# untitled.net
KiCad netlist of a schematic drawn in EAGLE
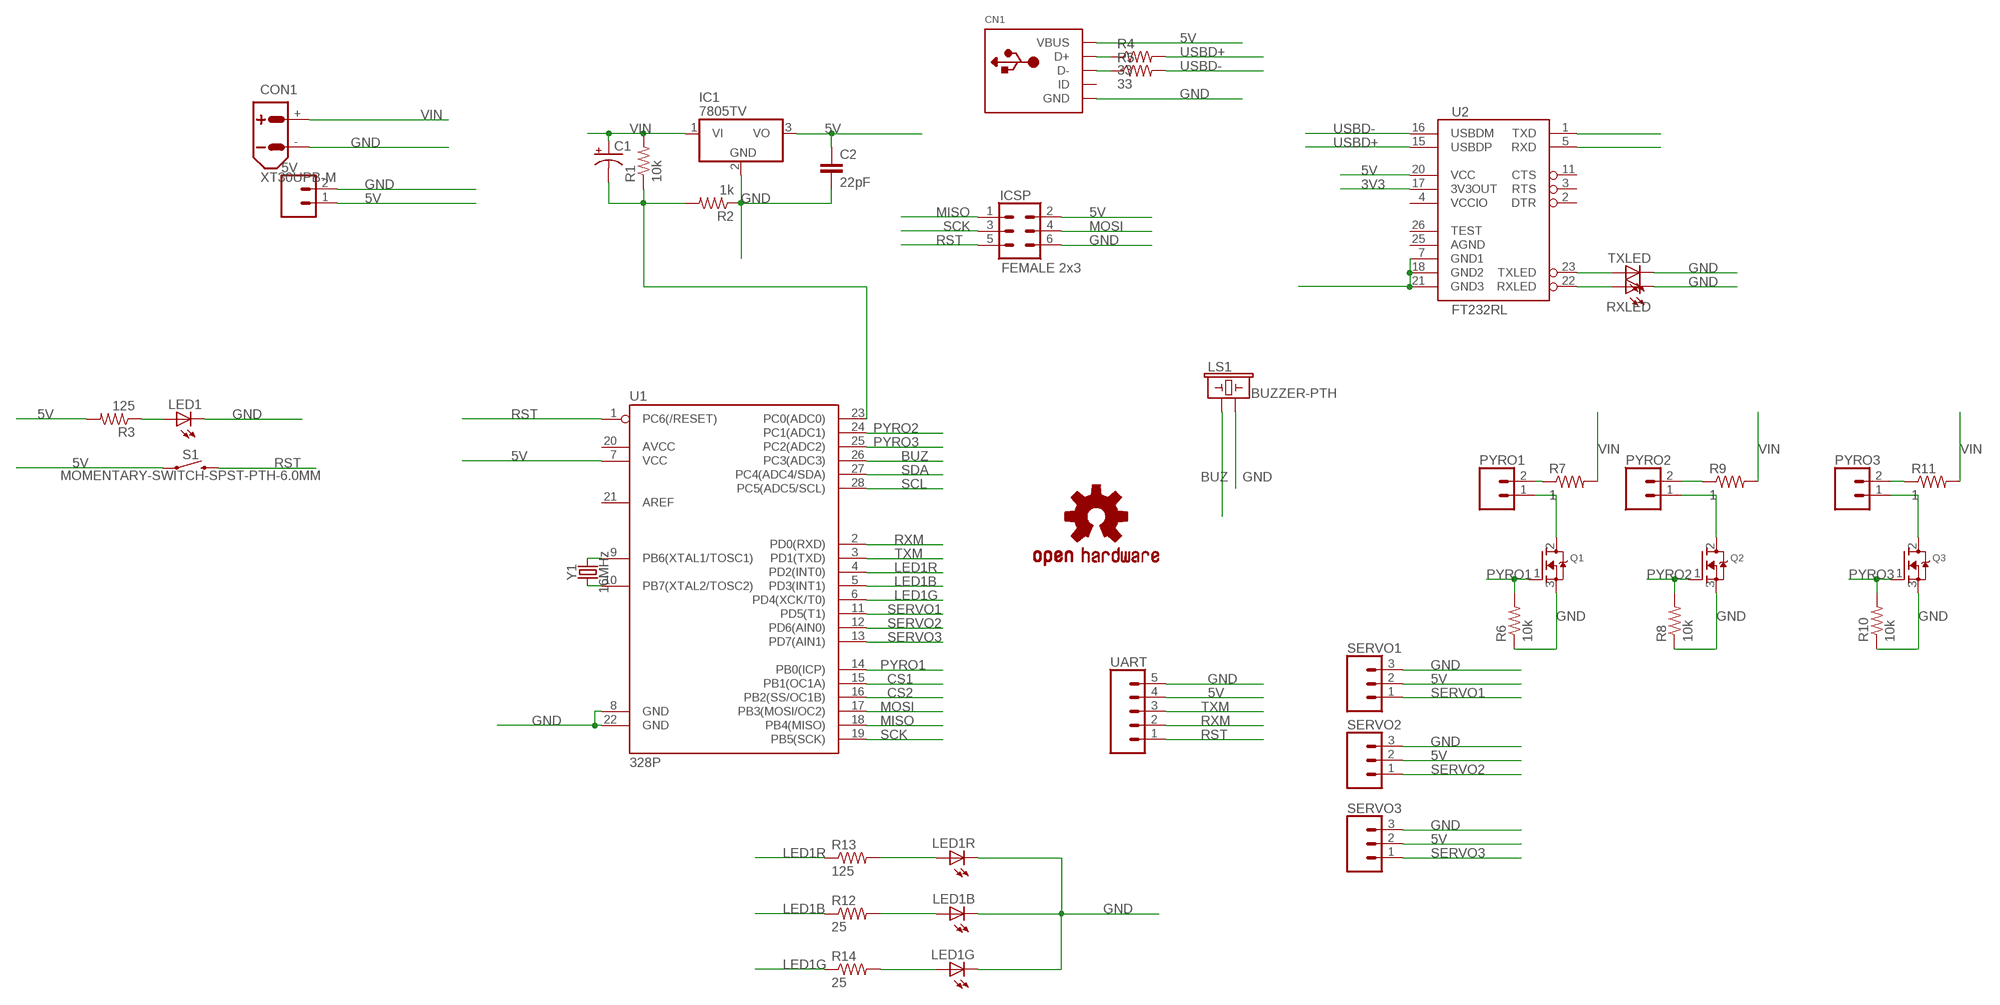
[diagram p0: schematic, sheet 1]

(export (version "E")
  (design (tool "Eeschema 10.0.6"))
  (components
    (comp (ref "5V")
      (value "CONN_02")
      (footprint "eagle-import:1X02")
      (libsource (lib "eagle-import") (part "CONN_02"))
    )
    (comp (ref "C1")
      (value "CPOL-USE3.5-8")
      (footprint "eagle-import:E3,5-8")
      (libsource (lib "eagle-import") (part "CPOL-USE3.5-8"))
    )
    (comp (ref "C2")
      (value "22pF")
      (footprint "eagle-import:CAP-PTH-2.54")
      (libsource (lib "eagle-import") (part "22PF-PTH-2.54MM-200V-5%"))
    )
    (comp (ref "CN1")
      (value "USBMINIB")
      (footprint "eagle-import:USB-MINIB")
      (libsource (lib "eagle-import") (part "USBMINIB"))
    )
    (comp (ref "CON1")
      (value "XT30UPB-M")
      (footprint "eagle-import:XT30UPB-M")
      (libsource (lib "eagle-import") (part "XT30UPB-M"))
    )
    (comp (ref "IC1")
      (value "7805TV")
      (footprint "eagle-import:TO220V")
      (libsource (lib "eagle-import") (part "78TV05"))
    )
    (comp (ref "ICSP")
      (value "FEMALE 2x3")
      (footprint "eagle-import:2X3")
      (libsource (lib "eagle-import") (part "CONN_03X2FEMALE"))
    )
    (comp (ref "LED1")
      (value "LED5MM")
      (footprint "eagle-import:LED5MM")
      (libsource (lib "eagle-import") (part "adafruit_420_LED5MM"))
    )
    (comp (ref "LED1B")
      (value "LED1B")
      (footprint "eagle-import:LED5MM")
      (libsource (lib "eagle-import") (part "LED5MM"))
    )
    (comp (ref "LED1G")
      (value "LED1G")
      (footprint "eagle-import:LED5MM")
      (libsource (lib "eagle-import") (part "LED5MM"))
    )
    (comp (ref "LED1R")
      (value "LED1R")
      (footprint "eagle-import:LED5MM")
      (libsource (lib "eagle-import") (part "LED5MM"))
    )
    (comp (ref "LOGO1")
      (value "OSHW-LOGOL")
      (footprint "eagle-import:OSHW-LOGO-L")
      (libsource (lib "eagle-import") (part "OSHW-LOGOL"))
    )
    (comp (ref "LS1")
      (value "BUZZER-PTH")
      (footprint "eagle-import:BUZZER-12MM")
      (libsource (lib "eagle-import") (part "BUZZER-PTH"))
    )
    (comp (ref "PYRO1")
      (value "CONN_025MM")
      (footprint "eagle-import:SCREWTERMINAL-5MM-2")
      (libsource (lib "eagle-import") (part "CONN_025MM"))
    )
    (comp (ref "PYRO2")
      (value "CONN_025MM")
      (footprint "eagle-import:SCREWTERMINAL-5MM-2")
      (libsource (lib "eagle-import") (part "CONN_025MM"))
    )
    (comp (ref "PYRO3")
      (value "CONN_025MM")
      (footprint "eagle-import:SCREWTERMINAL-5MM-2")
      (libsource (lib "eagle-import") (part "CONN_025MM"))
    )
    (comp (ref "Q1")
      (value "MOSFET-NGDS_TO220V")
      (footprint "eagle-import:TO220V")
      (libsource (lib "eagle-import") (part "MOSFET-NGDS_TO220V"))
    )
    (comp (ref "Q2")
      (value "MOSFET-NGDS_TO220V")
      (footprint "eagle-import:TO220V")
      (libsource (lib "eagle-import") (part "MOSFET-NGDS_TO220V"))
    )
    (comp (ref "Q3")
      (value "MOSFET-NGDS_TO220V")
      (footprint "eagle-import:TO220V")
      (libsource (lib "eagle-import") (part "MOSFET-NGDS_TO220V"))
    )
    (comp (ref "R1")
      (value "10k")
      (footprint "eagle-import:0805-THM")
      (libsource (lib "eagle-import") (part "adafruit_420_FLIPFLOP-RES"))
    )
    (comp (ref "R2")
      (value "1k")
      (footprint "eagle-import:0805-THM")
      (libsource (lib "eagle-import") (part "adafruit_420_FLIPFLOP-RES"))
    )
    (comp (ref "R3")
      (value "125")
      (footprint "eagle-import:0805-THM")
      (libsource (lib "eagle-import") (part "adafruit_420_FLIPFLOP-RES"))
    )
    (comp (ref "R4")
      (value "33")
      (footprint "eagle-import:0805-THM")
      (libsource (lib "eagle-import") (part "adafruit_420_FLIPFLOP-RES"))
    )
    (comp (ref "R5")
      (value "33")
      (footprint "eagle-import:0805-THM")
      (libsource (lib "eagle-import") (part "adafruit_420_FLIPFLOP-RES"))
    )
    (comp (ref "R6")
      (value "10k")
      (footprint "eagle-import:0805-THM")
      (libsource (lib "eagle-import") (part "FLIPFLOP-RES"))
    )
    (comp (ref "R7")
      (value "1")
      (footprint "eagle-import:0805-THM")
      (libsource (lib "eagle-import") (part "FLIPFLOP-RES"))
    )
    (comp (ref "R8")
      (value "10k")
      (footprint "eagle-import:0805-THM")
      (libsource (lib "eagle-import") (part "FLIPFLOP-RES"))
    )
    (comp (ref "R9")
      (value "1")
      (footprint "eagle-import:0805-THM")
      (libsource (lib "eagle-import") (part "FLIPFLOP-RES"))
    )
    (comp (ref "R10")
      (value "10k")
      (footprint "eagle-import:0805-THM")
      (libsource (lib "eagle-import") (part "FLIPFLOP-RES"))
    )
    (comp (ref "R11")
      (value "1")
      (footprint "eagle-import:0805-THM")
      (libsource (lib "eagle-import") (part "FLIPFLOP-RES"))
    )
    (comp (ref "R12")
      (value "25")
      (footprint "eagle-import:0805-THM")
      (libsource (lib "eagle-import") (part "FLIPFLOP-RES"))
    )
    (comp (ref "R13")
      (value "125")
      (footprint "eagle-import:0805-THM")
      (libsource (lib "eagle-import") (part "FLIPFLOP-RES"))
    )
    (comp (ref "R14")
      (value "25")
      (footprint "eagle-import:0805-THM")
      (libsource (lib "eagle-import") (part "FLIPFLOP-RES"))
    )
    (comp (ref "RXLED")
      (value "LED5MM")
      (footprint "eagle-import:LED5MM")
      (libsource (lib "eagle-import") (part "adafruit_420_LED5MM"))
    )
    (comp (ref "S1")
      (value "MOMENTARY-SWITCH-SPST-PTH-6.0MM")
      (footprint "eagle-import:TACTILE_SWITCH_PTH_6.0MM")
      (libsource (lib "eagle-import") (part "MOMENTARY-SWITCH-SPST-PTH-6.0MM"))
    )
    (comp (ref "SERVO1")
      (value "CONN_03")
      (footprint "eagle-import:1X03")
      (libsource (lib "eagle-import") (part "CONN_03"))
    )
    (comp (ref "SERVO2")
      (value "CONN_03")
      (footprint "eagle-import:1X03")
      (libsource (lib "eagle-import") (part "CONN_03"))
    )
    (comp (ref "SERVO3")
      (value "CONN_03")
      (footprint "eagle-import:1X03")
      (libsource (lib "eagle-import") (part "CONN_03"))
    )
    (comp (ref "TXLED")
      (value "LED5MM")
      (footprint "eagle-import:LED5MM")
      (libsource (lib "eagle-import") (part "adafruit_420_LED5MM"))
    )
    (comp (ref "U1")
      (value "328P")
      (footprint "eagle-import:DIP28")
      (libsource (lib "eagle-import") (part "ATMEGA328P_PDIP"))
    )
    (comp (ref "U2")
      (value "FT232RL")
      (footprint "eagle-import:SSOP28DB")
      (libsource (lib "eagle-import") (part "FT232RL-BASICSSOP"))
    )
    (comp (ref "UART")
      (value "CONN_05")
      (footprint "eagle-import:1X05")
      (libsource (lib "eagle-import") (part "CONN_05"))
    )
    (comp (ref "Y1")
      (value "16MHz")
      (footprint "eagle-import:HC49US")
      (libsource (lib "eagle-import") (part "CRYSTAL-16MHZPTH-HC49US"))
    )
  )
  (nets
    (net (code "1") (name "/3V3") (class "Default")
      (node (ref "U2") (pin "17") (pinfunction "3V3OUT_17") (pintype "output"))
    )
    (net (code "2") (name "/5V") (class "Default")
      (node (ref "5V") (pin "1") (pinfunction "1_1") (pintype "passive"))
      (node (ref "C2") (pin "1") (pinfunction "1_1") (pintype "passive"))
      (node (ref "CN1") (pin "VBUS") (pinfunction "VBUS_VBUS") (pintype "power_in"))
      (node (ref "IC1") (pin "3") (pinfunction "VO_3") (pintype "passive"))
      (node (ref "ICSP") (pin "2") (pinfunction "2_2") (pintype "bidirectional"))
      (node (ref "R3") (pin "2") (pinfunction "2_2") (pintype "passive"))
      (node (ref "S1") (pin "1") (pinfunction "1_1") (pintype "passive"))
      (node (ref "SERVO1") (pin "2") (pinfunction "2_2") (pintype "passive"))
      (node (ref "SERVO2") (pin "2") (pinfunction "2_2") (pintype "passive"))
      (node (ref "SERVO3") (pin "2") (pinfunction "2_2") (pintype "passive"))
      (node (ref "U1") (pin "7") (pinfunction "VCC_7") (pintype "bidirectional"))
      (node (ref "U2") (pin "20") (pinfunction "VCC_20") (pintype "power_in"))
      (node (ref "UART") (pin "4") (pinfunction "4_4") (pintype "passive"))
    )
    (net (code "3") (name "/AGND") (class "Default")
      (node (ref "U2") (pin "25") (pinfunction "AGND_25") (pintype "power_in"))
    )
    (net (code "4") (name "/BUZ") (class "Default")
      (node (ref "LS1") (pin "+") (pinfunction "1_+") (pintype "passive"))
      (node (ref "U1") (pin "26") (pinfunction "PC3(ADC3)_26") (pintype "bidirectional"))
    )
    (net (code "5") (name "/CS1") (class "Default")
      (node (ref "U1") (pin "15") (pinfunction "PB1(OC1A)_15") (pintype "bidirectional"))
    )
    (net (code "6") (name "/CS2") (class "Default")
      (node (ref "U1") (pin "16") (pinfunction "PB2(SS/OC1B)_16") (pintype "bidirectional"))
    )
    (net (code "7") (name "/GND") (class "Default")
      (node (ref "5V") (pin "2") (pinfunction "2_2") (pintype "passive"))
      (node (ref "C2") (pin "2") (pinfunction "2_2") (pintype "passive"))
      (node (ref "CN1") (pin "GND") (pinfunction "GND_GND") (pintype "power_in"))
      (node (ref "CON1") (pin "-") (pinfunction "-_-") (pintype "power_in"))
      (node (ref "IC1") (pin "2") (pinfunction "GND_2") (pintype "passive"))
      (node (ref "ICSP") (pin "6") (pinfunction "6_6") (pintype "bidirectional"))
      (node (ref "LED1") (pin "K") (pinfunction "C_K") (pintype "passive"))
      (node (ref "LED1B") (pin "K") (pinfunction "C_K") (pintype "passive"))
      (node (ref "LED1G") (pin "K") (pinfunction "C_K") (pintype "passive"))
      (node (ref "LED1R") (pin "K") (pinfunction "C_K") (pintype "passive"))
      (node (ref "LS1") (pin "-") (pinfunction "2_-") (pintype "passive"))
      (node (ref "Q1") (pin "3") (pinfunction "S_3") (pintype "bidirectional"))
      (node (ref "Q2") (pin "3") (pinfunction "S_3") (pintype "bidirectional"))
      (node (ref "Q3") (pin "3") (pinfunction "S_3") (pintype "bidirectional"))
      (node (ref "R10") (pin "1") (pinfunction "1_1") (pintype "passive"))
      (node (ref "R2") (pin "1") (pinfunction "1_1") (pintype "passive"))
      (node (ref "R6") (pin "1") (pinfunction "1_1") (pintype "passive"))
      (node (ref "R8") (pin "1") (pinfunction "1_1") (pintype "passive"))
      (node (ref "RXLED") (pin "K") (pinfunction "C_K") (pintype "passive"))
      (node (ref "SERVO1") (pin "3") (pinfunction "3_3") (pintype "passive"))
      (node (ref "SERVO2") (pin "3") (pinfunction "3_3") (pintype "passive"))
      (node (ref "SERVO3") (pin "3") (pinfunction "3_3") (pintype "passive"))
      (node (ref "TXLED") (pin "K") (pinfunction "C_K") (pintype "passive"))
      (node (ref "U1") (pin "22") (pinfunction "GND_22") (pintype "bidirectional"))
      (node (ref "U1") (pin "8") (pinfunction "GND_8") (pintype "bidirectional"))
      (node (ref "UART") (pin "5") (pinfunction "5_5") (pintype "passive"))
    )
    (net (code "8") (name "/LED1B") (class "Default")
      (node (ref "R12") (pin "1") (pinfunction "1_1") (pintype "passive"))
      (node (ref "U1") (pin "5") (pinfunction "PD3(INT1)_5") (pintype "bidirectional"))
    )
    (net (code "9") (name "/LED1G") (class "Default")
      (node (ref "R14") (pin "1") (pinfunction "1_1") (pintype "passive"))
      (node (ref "U1") (pin "6") (pinfunction "PD4(XCK/T0)_6") (pintype "bidirectional"))
    )
    (net (code "10") (name "/LED1R") (class "Default")
      (node (ref "R13") (pin "1") (pinfunction "1_1") (pintype "passive"))
      (node (ref "U1") (pin "4") (pinfunction "PD2(INT0)_4") (pintype "bidirectional"))
    )
    (net (code "11") (name "/MISO") (class "Default")
      (node (ref "ICSP") (pin "1") (pinfunction "1_1") (pintype "bidirectional"))
      (node (ref "U1") (pin "18") (pinfunction "PB4(MISO)_18") (pintype "bidirectional"))
    )
    (net (code "12") (name "/MOSI") (class "Default")
      (node (ref "ICSP") (pin "4") (pinfunction "4_4") (pintype "bidirectional"))
      (node (ref "U1") (pin "17") (pinfunction "PB3(MOSI/OC2)_17") (pintype "bidirectional"))
    )
    (net (code "13") (name "/PYRO1") (class "Default")
      (node (ref "Q1") (pin "1") (pinfunction "G_1") (pintype "bidirectional"))
      (node (ref "R6") (pin "2") (pinfunction "2_2") (pintype "passive"))
      (node (ref "U1") (pin "14") (pinfunction "PB0(ICP)_14") (pintype "bidirectional"))
    )
    (net (code "14") (name "/PYRO2") (class "Default")
      (node (ref "Q2") (pin "1") (pinfunction "G_1") (pintype "bidirectional"))
      (node (ref "R8") (pin "2") (pinfunction "2_2") (pintype "passive"))
      (node (ref "U1") (pin "24") (pinfunction "PC1(ADC1)_24") (pintype "bidirectional"))
    )
    (net (code "15") (name "/PYRO3") (class "Default")
      (node (ref "Q3") (pin "1") (pinfunction "G_1") (pintype "bidirectional"))
      (node (ref "R10") (pin "2") (pinfunction "2_2") (pintype "passive"))
      (node (ref "U1") (pin "25") (pinfunction "PC2(ADC2)_25") (pintype "bidirectional"))
    )
    (net (code "16") (name "/RST") (class "Default")
      (node (ref "ICSP") (pin "5") (pinfunction "5_5") (pintype "bidirectional"))
      (node (ref "S1") (pin "3") (pinfunction "2_3") (pintype "passive"))
      (node (ref "U1") (pin "1") (pinfunction "PC6(/RESET)_1") (pintype "bidirectional"))
      (node (ref "UART") (pin "1") (pinfunction "1_1") (pintype "passive"))
    )
    (net (code "17") (name "/RXM") (class "Default")
      (node (ref "U1") (pin "2") (pinfunction "PD0(RXD)_2") (pintype "bidirectional"))
      (node (ref "UART") (pin "2") (pinfunction "2_2") (pintype "passive"))
    )
    (net (code "18") (name "/SCK") (class "Default")
      (node (ref "ICSP") (pin "3") (pinfunction "3_3") (pintype "bidirectional"))
      (node (ref "U1") (pin "19") (pinfunction "PB5(SCK)_19") (pintype "bidirectional"))
    )
    (net (code "19") (name "/SCL") (class "Default")
      (node (ref "U1") (pin "28") (pinfunction "PC5(ADC5/SCL)_28") (pintype "bidirectional"))
    )
    (net (code "20") (name "/SDA") (class "Default")
      (node (ref "U1") (pin "27") (pinfunction "PC4(ADC4/SDA)_27") (pintype "bidirectional"))
    )
    (net (code "21") (name "/SERVO1") (class "Default")
      (node (ref "SERVO1") (pin "1") (pinfunction "1_1") (pintype "passive"))
      (node (ref "U1") (pin "11") (pinfunction "PD5(T1)_11") (pintype "bidirectional"))
    )
    (net (code "22") (name "/SERVO2") (class "Default")
      (node (ref "SERVO2") (pin "1") (pinfunction "1_1") (pintype "passive"))
      (node (ref "U1") (pin "12") (pinfunction "PD6(AIN0)_12") (pintype "bidirectional"))
    )
    (net (code "23") (name "/SERVO3") (class "Default")
      (node (ref "SERVO3") (pin "1") (pinfunction "1_1") (pintype "passive"))
      (node (ref "U1") (pin "13") (pinfunction "PD7(AIN1)_13") (pintype "bidirectional"))
    )
    (net (code "24") (name "/TXM") (class "Default")
      (node (ref "U1") (pin "3") (pinfunction "PD1(TXD)_3") (pintype "bidirectional"))
      (node (ref "UART") (pin "3") (pinfunction "3_3") (pintype "passive"))
    )
    (net (code "25") (name "/USBD+") (class "Default")
      (node (ref "R4") (pin "2") (pinfunction "2_2") (pintype "passive"))
      (node (ref "U2") (pin "15") (pinfunction "USBDP_15") (pintype "bidirectional"))
    )
    (net (code "26") (name "/USBD-") (class "Default")
      (node (ref "R5") (pin "2") (pinfunction "2_2") (pintype "passive"))
      (node (ref "U2") (pin "16") (pinfunction "USBDM_16") (pintype "bidirectional"))
    )
    (net (code "27") (name "/VCCIO") (class "Default")
      (node (ref "U2") (pin "4") (pinfunction "VCCIO_4") (pintype "power_in"))
    )
    (net (code "28") (name "/VIN") (class "Default")
      (node (ref "C1") (pin "+") (pinfunction "+_+") (pintype "passive"))
      (node (ref "CON1") (pin "+") (pinfunction "+_+") (pintype "power_in"))
      (node (ref "IC1") (pin "1") (pinfunction "VI_1") (pintype "input"))
      (node (ref "R1") (pin "2") (pinfunction "2_2") (pintype "passive"))
      (node (ref "R11") (pin "2") (pinfunction "2_2") (pintype "passive"))
      (node (ref "R7") (pin "2") (pinfunction "2_2") (pintype "passive"))
      (node (ref "R9") (pin "2") (pinfunction "2_2") (pintype "passive"))
    )
    (net (code "29") (name "Net-(CN1-PadD+)") (class "Default")
      (node (ref "CN1") (pin "D+") (pinfunction "D+_D+") (pintype "bidirectional"))
      (node (ref "R4") (pin "1") (pinfunction "1_1") (pintype "passive"))
    )
    (net (code "30") (name "Net-(CN1-PadD-)") (class "Default")
      (node (ref "CN1") (pin "D-") (pinfunction "D-_D-") (pintype "bidirectional"))
      (node (ref "R5") (pin "1") (pinfunction "1_1") (pintype "passive"))
    )
    (net (code "31") (name "Net-(LED1-PadA)") (class "Default")
      (node (ref "LED1") (pin "A") (pinfunction "A_A") (pintype "passive"))
      (node (ref "R3") (pin "1") (pinfunction "1_1") (pintype "passive"))
    )
    (net (code "32") (name "Net-(LED1B-PadA)") (class "Default")
      (node (ref "LED1B") (pin "A") (pinfunction "A_A") (pintype "passive"))
      (node (ref "R12") (pin "2") (pinfunction "2_2") (pintype "passive"))
    )
    (net (code "33") (name "Net-(LED1G-PadA)") (class "Default")
      (node (ref "LED1G") (pin "A") (pinfunction "A_A") (pintype "passive"))
      (node (ref "R14") (pin "2") (pinfunction "2_2") (pintype "passive"))
    )
    (net (code "34") (name "Net-(LED1R-PadA)") (class "Default")
      (node (ref "LED1R") (pin "A") (pinfunction "A_A") (pintype "passive"))
      (node (ref "R13") (pin "2") (pinfunction "2_2") (pintype "passive"))
    )
    (net (code "35") (name "Net-(PYRO1-Pad2)") (class "Default")
      (node (ref "PYRO1") (pin "2") (pinfunction "2_2") (pintype "passive"))
      (node (ref "R7") (pin "1") (pinfunction "1_1") (pintype "passive"))
    )
    (net (code "36") (name "Net-(PYRO2-Pad2)") (class "Default")
      (node (ref "PYRO2") (pin "2") (pinfunction "2_2") (pintype "passive"))
      (node (ref "R9") (pin "1") (pinfunction "1_1") (pintype "passive"))
    )
    (net (code "37") (name "Net-(PYRO3-Pad2)") (class "Default")
      (node (ref "PYRO3") (pin "2") (pinfunction "2_2") (pintype "passive"))
      (node (ref "R11") (pin "1") (pinfunction "1_1") (pintype "passive"))
    )
    (net (code "38") (name "Net-(Q1-D)") (class "Default")
      (node (ref "PYRO1") (pin "1") (pinfunction "1_1") (pintype "passive"))
      (node (ref "Q1") (pin "2") (pinfunction "D_2") (pintype "bidirectional"))
    )
    (net (code "39") (name "Net-(Q2-D)") (class "Default")
      (node (ref "PYRO2") (pin "1") (pinfunction "1_1") (pintype "passive"))
      (node (ref "Q2") (pin "2") (pinfunction "D_2") (pintype "bidirectional"))
    )
    (net (code "40") (name "Net-(Q3-D)") (class "Default")
      (node (ref "PYRO3") (pin "1") (pinfunction "1_1") (pintype "passive"))
      (node (ref "Q3") (pin "2") (pinfunction "D_2") (pintype "bidirectional"))
    )
    (net (code "41") (name "Net-(U1-PB6(XTAL1{slash}TOSC1))") (class "Default")
      (node (ref "U1") (pin "9") (pinfunction "PB6(XTAL1/TOSC1)_9") (pintype "bidirectional"))
      (node (ref "Y1") (pin "2") (pinfunction "2_2") (pintype "passive"))
    )
    (net (code "42") (name "Net-(U1-PB7(XTAL2{slash}TOSC2))") (class "Default")
      (node (ref "U1") (pin "10") (pinfunction "PB7(XTAL2/TOSC2)_10") (pintype "bidirectional"))
      (node (ref "Y1") (pin "1") (pinfunction "1_1") (pintype "passive"))
    )
    (net (code "43") (name "Net-(U1-PC0(ADC0))") (class "Default")
      (node (ref "C1") (pin "-") (pinfunction "-_-") (pintype "passive"))
      (node (ref "R1") (pin "1") (pinfunction "1_1") (pintype "passive"))
      (node (ref "R2") (pin "2") (pinfunction "2_2") (pintype "passive"))
      (node (ref "U1") (pin "23") (pinfunction "PC0(ADC0)_23") (pintype "bidirectional"))
    )
    (net (code "44") (name "Net-(U2-GND1)") (class "Default")
      (node (ref "U2") (pin "18") (pinfunction "GND2_18") (pintype "power_in"))
      (node (ref "U2") (pin "21") (pinfunction "GND3_21") (pintype "power_in"))
      (node (ref "U2") (pin "7") (pinfunction "GND1_7") (pintype "power_in"))
    )
    (net (code "45") (name "Net-(U2-RXLED)") (class "Default")
      (node (ref "RXLED") (pin "A") (pinfunction "A_A") (pintype "passive"))
      (node (ref "U2") (pin "22") (pinfunction "RXLED_22") (pintype "bidirectional"))
    )
    (net (code "46") (name "Net-(U2-TXLED)") (class "Default")
      (node (ref "TXLED") (pin "A") (pinfunction "A_A") (pintype "passive"))
      (node (ref "U2") (pin "23") (pinfunction "TXLED_23") (pintype "bidirectional"))
    )
    (net (code "47") (name "unconnected-(CN1-PadID)") (class "Default")
      (node (ref "CN1") (pin "ID") (pinfunction "ID_ID") (pintype "bidirectional"))
    )
    (net (code "48") (name "unconnected-(U1-AREF-Pad21)") (class "Default")
      (node (ref "U1") (pin "21") (pinfunction "AREF_21") (pintype "bidirectional"))
    )
    (net (code "49") (name "unconnected-(U1-AVCC-Pad20)") (class "Default")
      (node (ref "U1") (pin "20") (pinfunction "AVCC_20") (pintype "bidirectional"))
    )
    (net (code "50") (name "unconnected-(U2-CTS-Pad11)") (class "Default")
      (node (ref "U2") (pin "11") (pinfunction "CTS_11") (pintype "bidirectional"))
    )
    (net (code "51") (name "unconnected-(U2-DTR-Pad2)") (class "Default")
      (node (ref "U2") (pin "2") (pinfunction "DTR_2") (pintype "bidirectional"))
    )
    (net (code "52") (name "unconnected-(U2-RTS-Pad3)") (class "Default")
      (node (ref "U2") (pin "3") (pinfunction "RTS_3") (pintype "bidirectional"))
    )
    (net (code "53") (name "unconnected-(U2-RXD-Pad5)") (class "Default")
      (node (ref "U2") (pin "5") (pinfunction "RXD_5") (pintype "input"))
    )
    (net (code "54") (name "unconnected-(U2-TEST-Pad26)") (class "Default")
      (node (ref "U2") (pin "26") (pinfunction "TEST_26") (pintype "input"))
    )
    (net (code "55") (name "unconnected-(U2-TXD-Pad1)") (class "Default")
      (node (ref "U2") (pin "1") (pinfunction "TXD_1") (pintype "output"))
    )
  )
)
